# Mainboard.net
KiCad netlist of a schematic drawn in Altium Designer
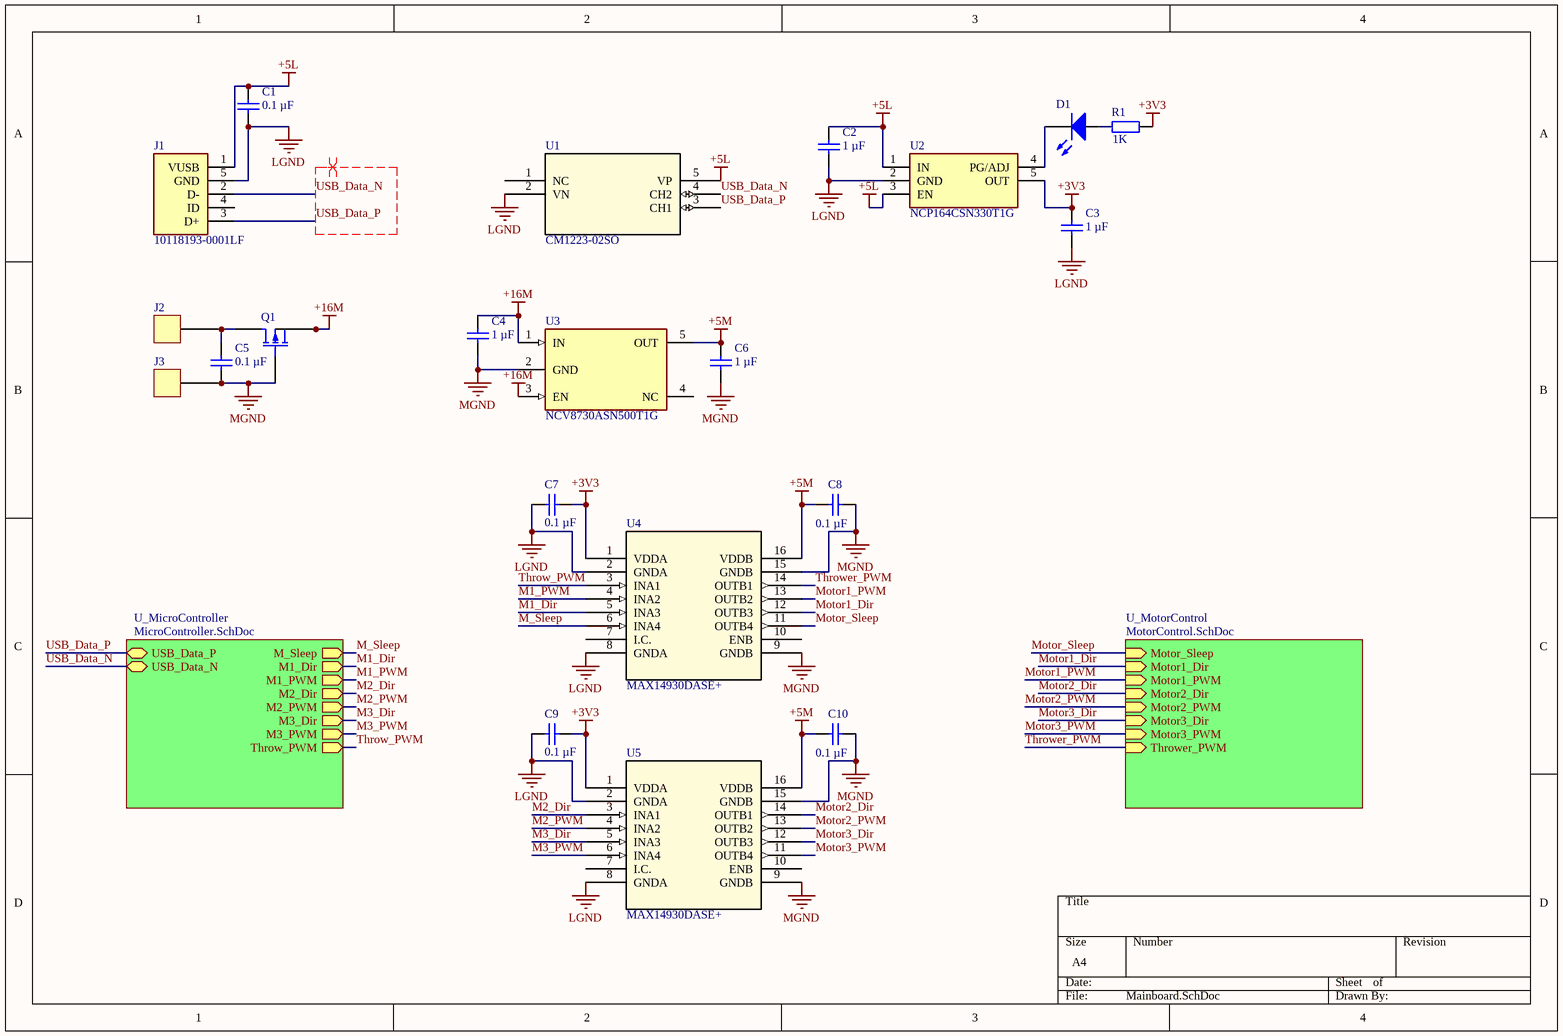
[diagram p0: Mainboard.SchDoc]

(export (version "E")
  (design (tool "Eeschema 10.0.6"))
  (components
    (comp (ref "C1")
      (value "0.1 µF")
      (footprint "CAP_0603")
      (description "Multilayer Ceramic Capacitors")
      (fields (field (name "TOLERANCE") "10%") (field (name "Comment") "MLCC"))
      (libsource (lib "Tartu University") (part "MLCC"))
    )
    (comp (ref "C2")
      (value "1 µF")
      (footprint "CAP_0603")
      (description "Multilayer Ceramic Capacitors")
      (fields (field (name "TOLERANCE") "10%") (field (name "Comment") "MLCC"))
      (libsource (lib "Tartu University") (part "MLCC"))
    )
    (comp (ref "C3")
      (value "1 µF")
      (footprint "CAP_0603")
      (description "Multilayer Ceramic Capacitors")
      (fields (field (name "TOLERANCE") "10%") (field (name "Comment") "MLCC"))
      (libsource (lib "Tartu University") (part "MLCC"))
    )
    (comp (ref "C4")
      (value "1 µF")
      (footprint "CAP_0603")
      (description "Multilayer Ceramic Capacitors")
      (fields (field (name "TOLERANCE") "10%") (field (name "Comment") "MLCC"))
      (libsource (lib "Tartu University") (part "MLCC"))
    )
    (comp (ref "C5")
      (value "0.1 µF")
      (footprint "CAP_0603")
      (description "Multilayer Ceramic Capacitors")
      (fields (field (name "TOLERANCE") "10%") (field (name "Comment") "MLCC"))
      (libsource (lib "Tartu University") (part "MLCC"))
    )
    (comp (ref "C6")
      (value "1 µF")
      (footprint "CAP_0603")
      (description "Multilayer Ceramic Capacitors")
      (fields (field (name "TOLERANCE") "10%") (field (name "Comment") "MLCC"))
      (libsource (lib "Tartu University") (part "MLCC"))
    )
    (comp (ref "C7")
      (value "0.1 µF")
      (footprint "CAP_0603")
      (description "Multilayer Ceramic Capacitors")
      (fields (field (name "TOLERANCE") "10%") (field (name "Comment") "MLCC"))
      (libsource (lib "Tartu University") (part "MLCC"))
    )
    (comp (ref "C8")
      (value "0.1 µF")
      (footprint "CAP_0603")
      (description "Multilayer Ceramic Capacitors")
      (fields (field (name "TOLERANCE") "10%") (field (name "Comment") "MLCC"))
      (libsource (lib "Tartu University") (part "MLCC"))
    )
    (comp (ref "C9")
      (value "0.1 µF")
      (footprint "CAP_0603")
      (description "Multilayer Ceramic Capacitors")
      (fields (field (name "TOLERANCE") "10%") (field (name "Comment") "MLCC"))
      (libsource (lib "Tartu University") (part "MLCC"))
    )
    (comp (ref "C10")
      (value "0.1 µF")
      (footprint "CAP_0603")
      (description "Multilayer Ceramic Capacitors")
      (fields (field (name "TOLERANCE") "10%") (field (name "Comment") "MLCC"))
      (libsource (lib "Tartu University") (part "MLCC"))
    )
    (comp (ref "D1")
      (value "LED")
      (footprint "0603_GREEN")
      (description "LED Emitters")
      (libsource (lib "Tartu University") (part "LED"))
    )
    (comp (ref "J1")
      (value "10118193-0001LF")
      (footprint "FCI_10118193-0001LF")
      (description "USB - micro B USB 2.0 Receptacle Connector 5 Position Surface Mount, Right Angle; Through Hole")
      (fields (field (name "MF") "Amphenol ICC"))
      (libsource (lib "Tartu University") (part "10118193-0001LF"))
    )
    (comp (ref "J2")
      (value "Generic Power Pad")
      (footprint "New footprint 1")
      (libsource (lib "Tartu University") (part "Power Pad"))
    )
    (comp (ref "J3")
      (value "Generic Power Pad")
      (footprint "New footprint 1")
      (libsource (lib "Tartu University") (part "Power Pad"))
    )
    (comp (ref "Q1")
      (value "BUK6Y10-30P")
      (footprint "NXP-SOT669_N")
      (description "P-Channel Standard Level MOSFET SOT669-5")
      (fields (field (name "PARTNUMBER") "BUK7Y4R4-40EX"))
      (libsource (lib "Tartu University") (part "CMP-1259-00420-1"))
    )
    (comp (ref "R1")
      (value "1K")
      (footprint "RC0603N")
      (description "Chip Resistors")
      (fields (field (name "Comment") "RES"))
      (libsource (lib "Tartu University") (part "MELF"))
    )
    (comp (ref "U1")
      (value "CM1223-02SO")
      (footprint "SOT23-5_3X1P7_ONS")
      (description "No Description Available")
      (fields (field (name "COPYRIGHT") "Copyright (C) 2022 Ultra Librarian. All rights reserved."))
      (libsource (lib "Tartu University") (part "CM1223-02SO"))
    )
    (comp (ref "U2")
      (value "NCP164CSN330T1G")
      (footprint "SamacSys:SOT95P275X110-5N")
      (description "Integrated Circuit")
      (fields (field (name "MOUSER PART NUMBER") "863-NCP164CSN330T1G"))
      (libsource (lib "SamacSys") (part "NCP164CSN330T1G"))
    )
    (comp (ref "U3")
      (value "NCV8730ASN500T1G")
      (footprint "FP-483-MFG")
      (description "LDO Regulator TSOP-5")
      (libsource (lib "Components - 15.10.22 - 22.46") (part "NCV8730ASN500T1G"))
    )
    (comp (ref "U4")
      (value "MAX14930DASE+")
      (footprint "21-0041_S16+1_MXM")
      (description "No Description Available")
      (fields (field (name "COPYRIGHT") "Copyright (C) 2022 Ultra Librarian. All rights reserved."))
      (libsource (lib "MAX14930DASE&plus_") (part "MAX14930DASE+"))
    )
    (comp (ref "U5")
      (value "MAX14930DASE+")
      (footprint "21-0041_S16+1_MXM")
      (description "No Description Available")
      (fields (field (name "COPYRIGHT") "Copyright (C) 2022 Ultra Librarian. All rights reserved."))
      (libsource (lib "MAX14930DASE&plus_") (part "MAX14930DASE+"))
    )
  )
  (nets
    (net (code "1") (name "+3V3") (class "Default")
      (node (ref "C3") (pin "2") (pinfunction "2_2") (pintype "passive"))
      (node (ref "C7") (pin "1") (pinfunction "1_1") (pintype "passive"))
      (node (ref "C9") (pin "1") (pinfunction "1_1") (pintype "passive"))
      (node (ref "R1") (pin "2") (pinfunction "2_2") (pintype "passive"))
      (node (ref "U2") (pin "5") (pinfunction "OUT_5") (pintype "passive"))
      (node (ref "U4") (pin "1") (pinfunction "VDDA_1") (pintype "power_in"))
      (node (ref "U5") (pin "1") (pinfunction "VDDA_1") (pintype "power_in"))
    )
    (net (code "2") (name "+5L") (class "Default")
      (node (ref "C1") (pin "2") (pinfunction "2_2") (pintype "passive"))
      (node (ref "C2") (pin "2") (pinfunction "2_2") (pintype "passive"))
      (node (ref "J1") (pin "1") (pinfunction "VUSB_1") (pintype "passive"))
      (node (ref "U1") (pin "5") (pinfunction "VP_5") (pintype "power_in"))
      (node (ref "U2") (pin "1") (pinfunction "IN_1") (pintype "passive"))
      (node (ref "U2") (pin "3") (pinfunction "EN_3") (pintype "passive"))
    )
    (net (code "3") (name "+5M") (class "Default")
      (node (ref "C10") (pin "2") (pinfunction "2_2") (pintype "passive"))
      (node (ref "C6") (pin "2") (pinfunction "2_2") (pintype "passive"))
      (node (ref "C8") (pin "2") (pinfunction "2_2") (pintype "passive"))
      (node (ref "U3") (pin "5") (pinfunction "OUT_5") (pintype "power_in"))
      (node (ref "U4") (pin "16") (pinfunction "VDDB_16") (pintype "power_in"))
      (node (ref "U5") (pin "16") (pinfunction "VDDB_16") (pintype "power_in"))
    )
    (net (code "4") (name "+16M") (class "Default")
      (node (ref "C4") (pin "2") (pinfunction "2_2") (pintype "passive"))
      (node (ref "Q1") (pin "1") (pinfunction "S_1") (pintype "passive"))
      (node (ref "Q1") (pin "2") (pinfunction "S_2") (pintype "passive"))
      (node (ref "Q1") (pin "3") (pinfunction "S_3") (pintype "passive"))
      (node (ref "U3") (pin "1") (pinfunction "IN_1") (pintype "input"))
      (node (ref "U3") (pin "3") (pinfunction "EN_3") (pintype "input"))
    )
    (net (code "5") (name "/M1_Dir") (class "Default")
      (node (ref "U4") (pin "5") (pinfunction "INA3_5") (pintype "input"))
    )
    (net (code "6") (name "/M1_PWM") (class "Default")
      (node (ref "U4") (pin "4") (pinfunction "INA2_4") (pintype "input"))
    )
    (net (code "7") (name "/M2_Dir") (class "Default")
      (node (ref "U5") (pin "3") (pinfunction "INA1_3") (pintype "input"))
    )
    (net (code "8") (name "/M2_PWM") (class "Default")
      (node (ref "U5") (pin "4") (pinfunction "INA2_4") (pintype "input"))
    )
    (net (code "9") (name "/M3_Dir") (class "Default")
      (node (ref "U5") (pin "5") (pinfunction "INA3_5") (pintype "input"))
    )
    (net (code "10") (name "/M3_PWM") (class "Default")
      (node (ref "U5") (pin "6") (pinfunction "INA4_6") (pintype "input"))
    )
    (net (code "11") (name "/M_Sleep") (class "Default")
      (node (ref "U4") (pin "6") (pinfunction "INA4_6") (pintype "input"))
    )
    (net (code "12") (name "/Motor1_Dir") (class "Default")
      (node (ref "U4") (pin "12") (pinfunction "OUTB3_12") (pintype "output"))
    )
    (net (code "13") (name "/Motor1_PWM") (class "Default")
      (node (ref "U4") (pin "13") (pinfunction "OUTB2_13") (pintype "output"))
    )
    (net (code "14") (name "/Motor2_Dir") (class "Default")
      (node (ref "U5") (pin "14") (pinfunction "OUTB1_14") (pintype "output"))
    )
    (net (code "15") (name "/Motor2_PWM") (class "Default")
      (node (ref "U5") (pin "13") (pinfunction "OUTB2_13") (pintype "output"))
    )
    (net (code "16") (name "/Motor3_Dir") (class "Default")
      (node (ref "U5") (pin "12") (pinfunction "OUTB3_12") (pintype "output"))
    )
    (net (code "17") (name "/Motor3_PWM") (class "Default")
      (node (ref "U5") (pin "11") (pinfunction "OUTB4_11") (pintype "output"))
    )
    (net (code "18") (name "/Motor_Sleep") (class "Default")
      (node (ref "U4") (pin "11") (pinfunction "OUTB4_11") (pintype "output"))
    )
    (net (code "19") (name "/Throw_PWM") (class "Default")
      (node (ref "U4") (pin "3") (pinfunction "INA1_3") (pintype "input"))
    )
    (net (code "20") (name "/Thrower_PWM") (class "Default")
      (node (ref "U4") (pin "14") (pinfunction "OUTB1_14") (pintype "output"))
    )
    (net (code "21") (name "/USB_Data_N") (class "Default")
      (node (ref "J1") (pin "2") (pinfunction "D-_2") (pintype "passive"))
      (node (ref "U1") (pin "4") (pinfunction "CH2_4") (pintype "bidirectional"))
    )
    (net (code "22") (name "/USB_Data_P") (class "Default")
      (node (ref "J1") (pin "3") (pinfunction "D+_3") (pintype "passive"))
      (node (ref "U1") (pin "3") (pinfunction "CH1_3") (pintype "bidirectional"))
    )
    (net (code "23") (name "LGND") (class "Default")
      (node (ref "C1") (pin "1") (pinfunction "1_1") (pintype "passive"))
      (node (ref "C2") (pin "1") (pinfunction "1_1") (pintype "passive"))
      (node (ref "C3") (pin "1") (pinfunction "1_1") (pintype "passive"))
      (node (ref "C7") (pin "2") (pinfunction "2_2") (pintype "passive"))
      (node (ref "C9") (pin "2") (pinfunction "2_2") (pintype "passive"))
      (node (ref "J1") (pin "5") (pinfunction "GND_5") (pintype "passive"))
      (node (ref "U1") (pin "2") (pinfunction "VN_2") (pintype "passive"))
      (node (ref "U2") (pin "2") (pinfunction "GND_2") (pintype "passive"))
      (node (ref "U4") (pin "2") (pinfunction "GNDA_2") (pintype "passive"))
      (node (ref "U4") (pin "8") (pinfunction "GNDA_8") (pintype "passive"))
      (node (ref "U5") (pin "2") (pinfunction "GNDA_2") (pintype "passive"))
      (node (ref "U5") (pin "8") (pinfunction "GNDA_8") (pintype "passive"))
    )
    (net (code "24") (name "MGND") (class "Default")
      (node (ref "C10") (pin "1") (pinfunction "1_1") (pintype "passive"))
      (node (ref "C4") (pin "1") (pinfunction "1_1") (pintype "passive"))
      (node (ref "C5") (pin "1") (pinfunction "1_1") (pintype "passive"))
      (node (ref "C6") (pin "1") (pinfunction "1_1") (pintype "passive"))
      (node (ref "C8") (pin "1") (pinfunction "1_1") (pintype "passive"))
      (node (ref "J3") (pin "1") (pinfunction "1_1") (pintype "passive"))
      (node (ref "Q1") (pin "4") (pinfunction "G_4") (pintype "passive"))
      (node (ref "U3") (pin "2") (pinfunction "GND_2") (pintype "passive"))
      (node (ref "U4") (pin "15") (pinfunction "GNDB_15") (pintype "passive"))
      (node (ref "U4") (pin "9") (pinfunction "GNDB_9") (pintype "passive"))
      (node (ref "U5") (pin "15") (pinfunction "GNDB_15") (pintype "passive"))
      (node (ref "U5") (pin "9") (pinfunction "GNDB_9") (pintype "passive"))
    )
    (net (code "25") (name "Net-(D1-A)") (class "Default")
      (node (ref "D1") (pin "1") (pinfunction "A_1") (pintype "passive"))
      (node (ref "R1") (pin "1") (pinfunction "1_1") (pintype "passive"))
    )
    (net (code "26") (name "Net-(D1-K)") (class "Default")
      (node (ref "D1") (pin "2") (pinfunction "K_2") (pintype "passive"))
      (node (ref "U2") (pin "4") (pinfunction "PG/ADJ_4") (pintype "passive"))
    )
    (net (code "27") (name "Net-(Q1-D)") (class "Default")
      (node (ref "C5") (pin "2") (pinfunction "2_2") (pintype "passive"))
      (node (ref "J2") (pin "1") (pinfunction "1_1") (pintype "passive"))
      (node (ref "Q1") (pin "5") (pinfunction "D_5") (pintype "passive"))
    )
    (net (code "28") (name "unconnected-(J1-ID-Pad4)") (class "Default")
      (node (ref "J1") (pin "4") (pinfunction "ID_4") (pintype "passive"))
    )
    (net (code "29") (name "unconnected-(U1-NC-Pad1)") (class "Default")
      (node (ref "U1") (pin "1") (pinfunction "NC_1") (pintype "passive"))
    )
    (net (code "30") (name "unconnected-(U3-NC-Pad4)") (class "Default")
      (node (ref "U3") (pin "4") (pinfunction "NC_4") (pintype "passive"))
    )
    (net (code "31") (name "unconnected-(U4-ENB-Pad10)") (class "Default")
      (node (ref "U4") (pin "10") (pinfunction "ENB_10") (pintype "passive"))
    )
    (net (code "32") (name "unconnected-(U4-I.C.-Pad7)") (class "Default")
      (node (ref "U4") (pin "7") (pinfunction "I.C._7") (pintype "passive"))
    )
    (net (code "33") (name "unconnected-(U5-ENB-Pad10)") (class "Default")
      (node (ref "U5") (pin "10") (pinfunction "ENB_10") (pintype "passive"))
    )
    (net (code "34") (name "unconnected-(U5-I.C.-Pad7)") (class "Default")
      (node (ref "U5") (pin "7") (pinfunction "I.C._7") (pintype "passive"))
    )
  )
)
